# Proto_ARM.net
KiCad netlist of a schematic drawn in EAGLE
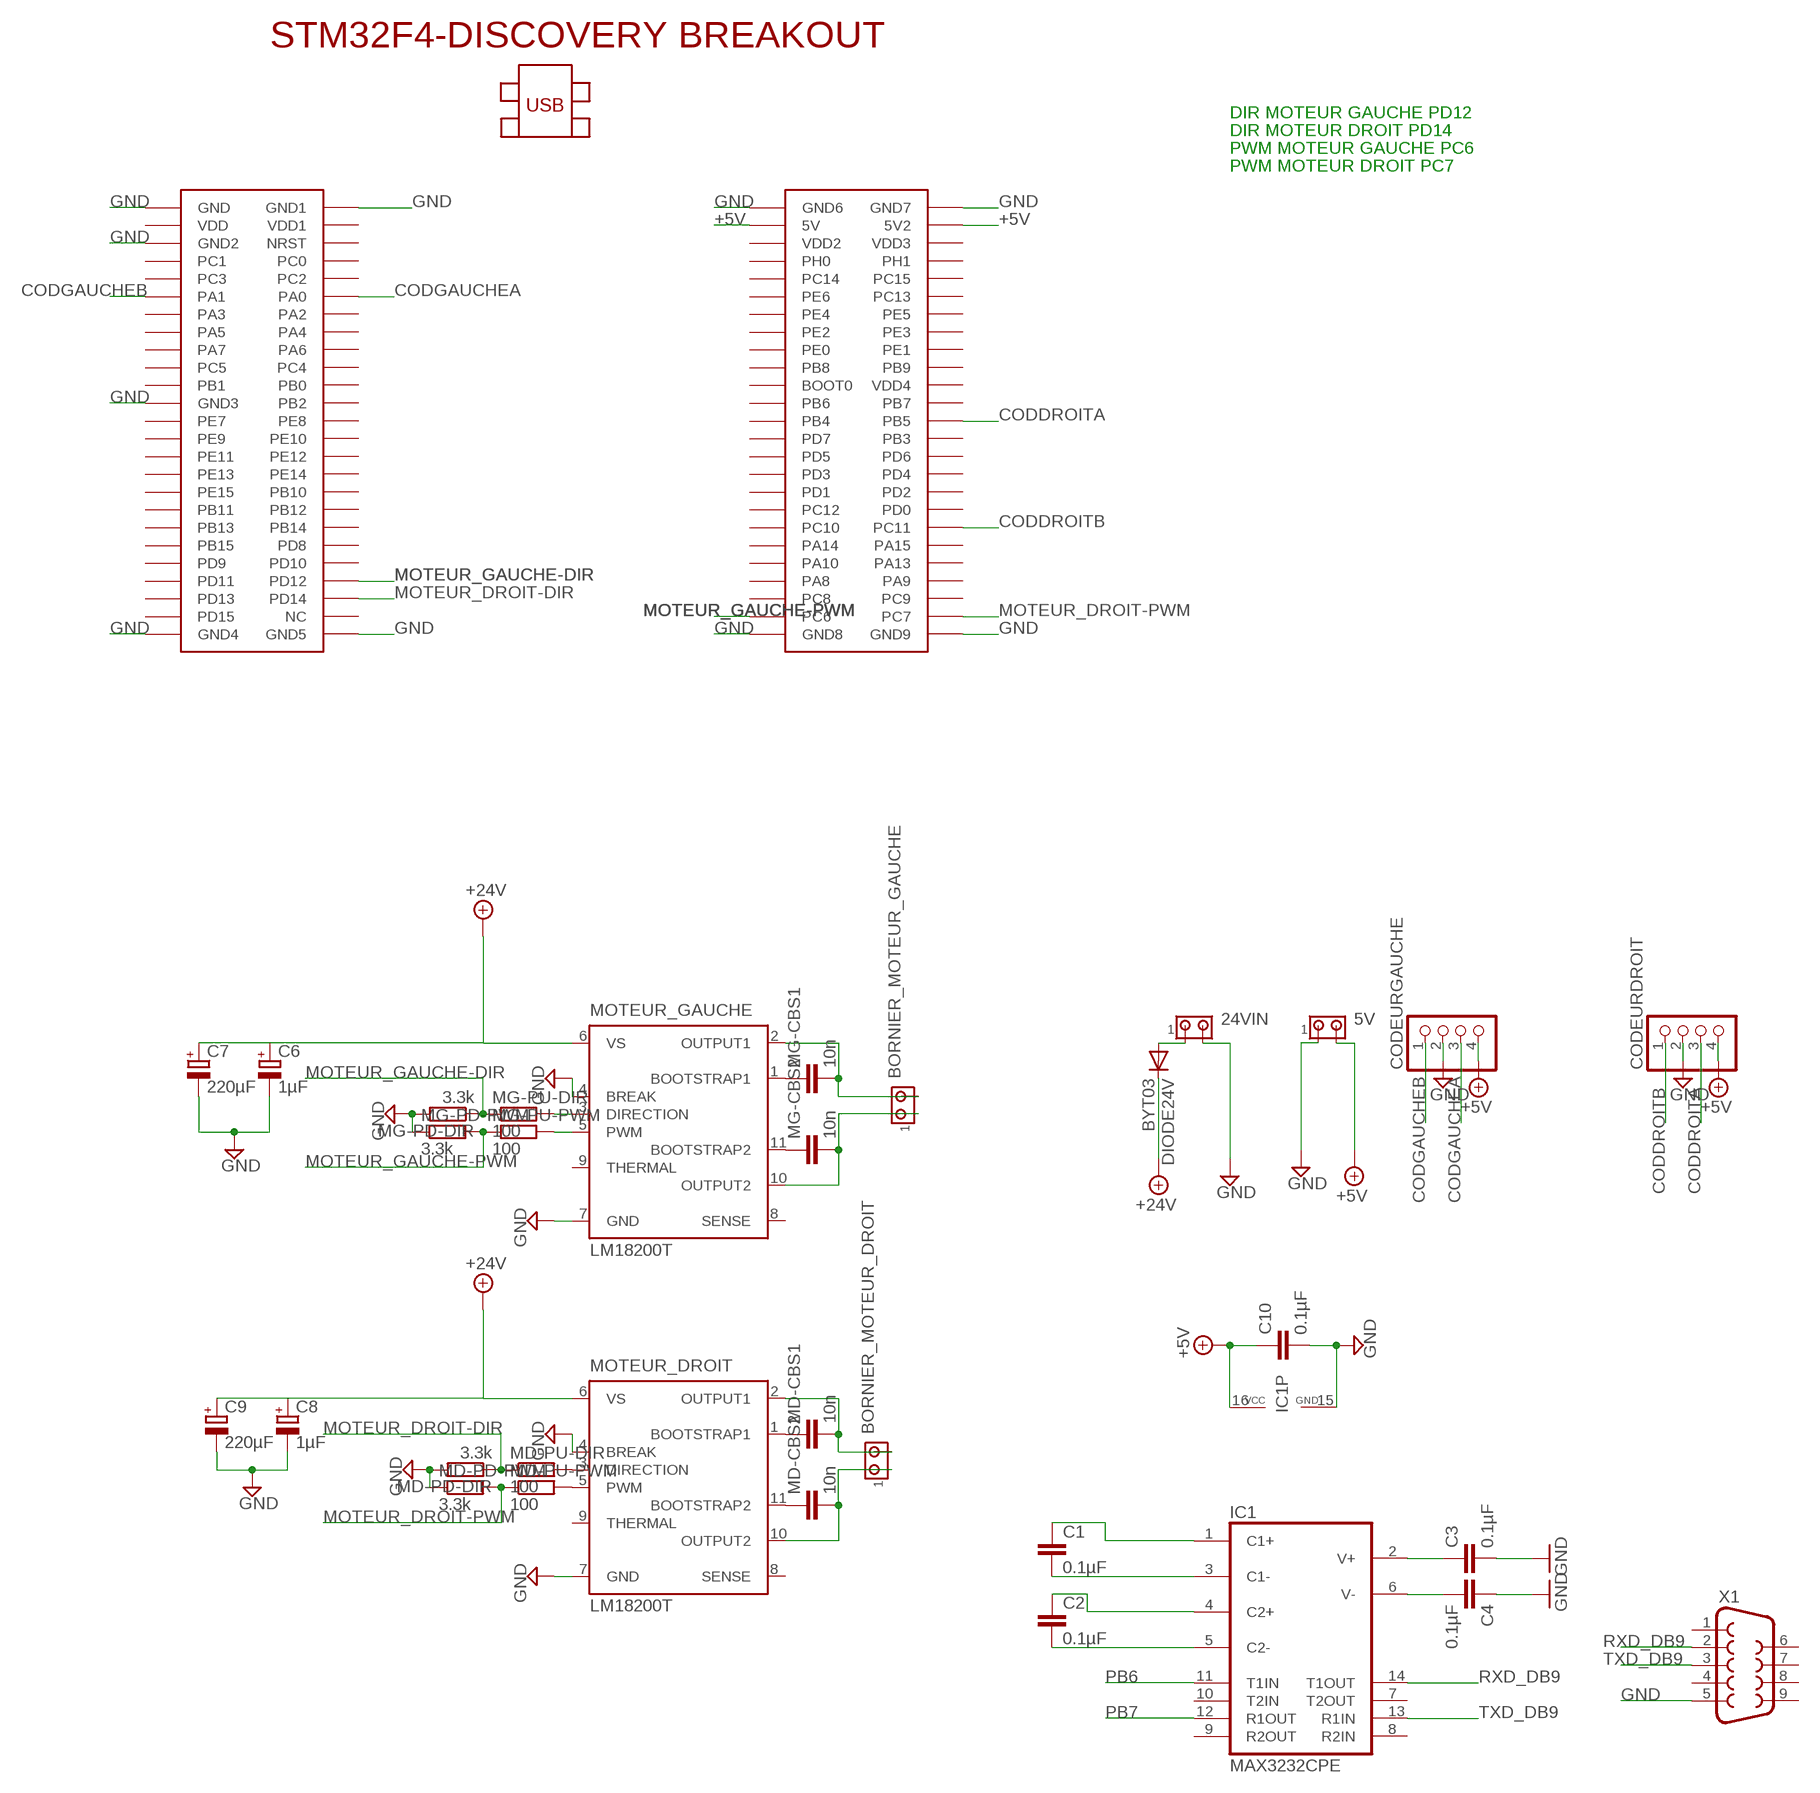
[diagram p0: schematic, sheet 1]

(export (version "E")
  (design (tool "Eeschema 10.0.6"))
  (components
    (comp (ref "5V")
      (value "MTA02-156")
      (footprint "eagle-import:1X2MTA")
      (libsource (lib "eagle-import") (part "MTA02-156"))
    )
    (comp (ref "24VIN")
      (value "MTA02-156")
      (footprint "eagle-import:1X2MTA")
      (libsource (lib "eagle-import") (part "MTA02-156"))
    )
    (comp (ref "BORNIER_MOTEUR_DROIT")
      (value "MTA02-156")
      (footprint "eagle-import:1X2MTA")
      (libsource (lib "eagle-import") (part "MTA02-156"))
    )
    (comp (ref "BORNIER_MOTEUR_GAUCHE")
      (value "MTA02-156")
      (footprint "eagle-import:1X2MTA")
      (libsource (lib "eagle-import") (part "MTA02-156"))
    )
    (comp (ref "C1")
      (value "0.1µF")
      (footprint "eagle-import:C050-035X075")
      (libsource (lib "eagle-import") (part "C-EU050-035X075"))
    )
    (comp (ref "C2")
      (value "0.1µF")
      (footprint "eagle-import:C050-035X075")
      (libsource (lib "eagle-import") (part "C-EU050-035X075"))
    )
    (comp (ref "C3")
      (value "0.1µF")
      (footprint "eagle-import:C050-035X075")
      (libsource (lib "eagle-import") (part "C-EU050-035X075"))
    )
    (comp (ref "C4")
      (value "0.1µF")
      (footprint "eagle-import:C050-035X075")
      (libsource (lib "eagle-import") (part "C-EU050-035X075"))
    )
    (comp (ref "C6")
      (value "1µF")
      (footprint "eagle-import:E3,5-8")
      (libsource (lib "eagle-import") (part "CPOL-EUE3.5-8"))
    )
    (comp (ref "C7")
      (value "220µF")
      (footprint "eagle-import:E3,5-8")
      (libsource (lib "eagle-import") (part "CPOL-EUE3.5-8"))
    )
    (comp (ref "C8")
      (value "1µF")
      (footprint "eagle-import:E3,5-8")
      (libsource (lib "eagle-import") (part "CPOL-EUE3.5-8"))
    )
    (comp (ref "C9")
      (value "220µF")
      (footprint "eagle-import:E3,5-8")
      (libsource (lib "eagle-import") (part "CPOL-EUE3.5-8"))
    )
    (comp (ref "C10")
      (value "0.1µF")
      (footprint "eagle-import:C050-035X075")
      (libsource (lib "eagle-import") (part "C-EU050-035X075"))
    )
    (comp (ref "CODEURDROIT")
      (value "PINHD-1X4")
      (footprint "eagle-import:1X04")
      (libsource (lib "eagle-import") (part "PINHD-1X4"))
    )
    (comp (ref "CODEURGAUCHE")
      (value "PINHD-1X4")
      (footprint "eagle-import:1X04")
      (libsource (lib "eagle-import") (part "PINHD-1X4"))
    )
    (comp (ref "DIODE24V")
      (value "BYT03")
      (footprint "eagle-import:DO27-15")
      (libsource (lib "eagle-import") (part "BYT03"))
    )
    (comp (ref "IC1")
      (value "MAX3232CPE")
      (footprint "eagle-import:DIL16")
      (fields
        (field (name "MF") "MAXIM")
        (field (name "MPN") "MAX3232CPE+")
        (field (name "MF_1") "MAXIM")
        (field (name "MPN_1") "MAX3232CPE+")
        (field (name "OC_FARNELL") "9724494")
        (field (name "OC_NEWARK") "68K4626")
      )
      (libsource (lib "eagle-import") (part "MAX3232PEC"))
    )
    (comp (ref "MD-CBS1")
      (value "10n")
      (footprint "eagle-import:C050-025X075")
      (libsource (lib "eagle-import") (part "C-EU050-025X075"))
    )
    (comp (ref "MD-CBS2")
      (value "10n")
      (footprint "eagle-import:C050-025X075")
      (libsource (lib "eagle-import") (part "C-EU050-025X075"))
    )
    (comp (ref "MD-PD-DIR")
      (value "3.3k")
      (footprint "eagle-import:0207_7")
      (libsource (lib "eagle-import") (part "R-EU_0207/7"))
    )
    (comp (ref "MD-PD-PWM")
      (value "3.3k")
      (footprint "eagle-import:0207_7")
      (libsource (lib "eagle-import") (part "R-EU_0207/7"))
    )
    (comp (ref "MD-PU-DIR")
      (value "100")
      (footprint "eagle-import:0207_7")
      (libsource (lib "eagle-import") (part "R-EU_0207/7"))
    )
    (comp (ref "MD-PU-PWM")
      (value "100")
      (footprint "eagle-import:0207_7")
      (libsource (lib "eagle-import") (part "R-EU_0207/7"))
    )
    (comp (ref "MG-CBS1")
      (value "10n")
      (footprint "eagle-import:C050-025X075")
      (libsource (lib "eagle-import") (part "C-EU050-025X075"))
    )
    (comp (ref "MG-CBS2")
      (value "10n")
      (footprint "eagle-import:C050-025X075")
      (libsource (lib "eagle-import") (part "C-EU050-025X075"))
    )
    (comp (ref "MG-PD-DIR")
      (value "3.3k")
      (footprint "eagle-import:0207_7")
      (libsource (lib "eagle-import") (part "R-EU_0207/7"))
    )
    (comp (ref "MG-PD-PWM")
      (value "3.3k")
      (footprint "eagle-import:0207_7")
      (libsource (lib "eagle-import") (part "R-EU_0207/7"))
    )
    (comp (ref "MG-PU-DIR")
      (value "100")
      (footprint "eagle-import:0207_7")
      (libsource (lib "eagle-import") (part "R-EU_0207/7"))
    )
    (comp (ref "MG-PU-PWM")
      (value "100")
      (footprint "eagle-import:0207_7")
      (libsource (lib "eagle-import") (part "R-EU_0207/7"))
    )
    (comp (ref "MOTEUR_DROIT")
      (value "LM18200T")
      (footprint "eagle-import:TO-220-11")
      (libsource (lib "eagle-import") (part "LM18200T"))
    )
    (comp (ref "MOTEUR_GAUCHE")
      (value "LM18200T")
      (footprint "eagle-import:TO-220-11")
      (libsource (lib "eagle-import") (part "LM18200T"))
    )
    (comp (ref "U$1")
      (value "STM32F4-DISCOVERY")
      (footprint "eagle-import:STM32F4-DISCOVERY")
      (libsource (lib "eagle-import") (part "STM32F4-DISCOVERY"))
    )
    (comp (ref "X1")
      (value "F09HP")
      (footprint "eagle-import:F09HP")
      (libsource (lib "eagle-import") (part "F09HP"))
    )
  )
  (nets
    (net (code "1") (name "+5V") (class "Default")
      (node (ref "5V") (pin "2") (pinfunction "2_2") (pintype "passive"))
      (node (ref "C10") (pin "1") (pinfunction "1_1") (pintype "passive"))
      (node (ref "CODEURDROIT") (pin "4") (pinfunction "4_4") (pintype "passive"))
      (node (ref "CODEURGAUCHE") (pin "4") (pinfunction "4_4") (pintype "passive"))
      (node (ref "IC1") (pin "16") (pinfunction "VCC_16") (pintype "power_in"))
      (node (ref "U$1") (pin "P$53") (pinfunction "5V_P$53") (pintype "bidirectional"))
      (node (ref "U$1") (pin "P$54") (pinfunction "5V2_P$54") (pintype "bidirectional"))
    )
    (net (code "2") (name "+24V") (class "Default")
      (node (ref "C6") (pin "+") (pinfunction "+_+") (pintype "passive"))
      (node (ref "C7") (pin "+") (pinfunction "+_+") (pintype "passive"))
      (node (ref "C8") (pin "+") (pinfunction "+_+") (pintype "passive"))
      (node (ref "C9") (pin "+") (pinfunction "+_+") (pintype "passive"))
      (node (ref "DIODE24V") (pin "C") (pinfunction "C_C") (pintype "passive"))
      (node (ref "MOTEUR_DROIT") (pin "6") (pinfunction "VS_6") (pintype "power_in"))
      (node (ref "MOTEUR_GAUCHE") (pin "6") (pinfunction "VS_6") (pintype "power_in"))
    )
    (net (code "3") (name "/CODDROITA") (class "Default")
      (node (ref "CODEURDROIT") (pin "3") (pinfunction "3_3") (pintype "passive"))
      (node (ref "U$1") (pin "P$76") (pinfunction "PB5_P$76") (pintype "bidirectional"))
    )
    (net (code "4") (name "/CODDROITB") (class "Default")
      (node (ref "CODEURDROIT") (pin "1") (pinfunction "1_1") (pintype "passive"))
      (node (ref "U$1") (pin "P$88") (pinfunction "PC11_P$88") (pintype "bidirectional"))
    )
    (net (code "5") (name "/CODGAUCHEA") (class "Default")
      (node (ref "CODEURGAUCHE") (pin "3") (pinfunction "3_3") (pintype "passive"))
      (node (ref "U$1") (pin "P$12") (pinfunction "PA0_P$12") (pintype "bidirectional"))
    )
    (net (code "6") (name "/CODGAUCHEB") (class "Default")
      (node (ref "CODEURGAUCHE") (pin "1") (pinfunction "1_1") (pintype "passive"))
      (node (ref "U$1") (pin "P$11") (pinfunction "PA1_P$11") (pintype "bidirectional"))
    )
    (net (code "7") (name "/MOTEUR_DROIT-DIR") (class "Default")
      (node (ref "MD-PD-DIR") (pin "1") (pinfunction "1_1") (pintype "passive"))
      (node (ref "MD-PU-DIR") (pin "1") (pinfunction "1_1") (pintype "passive"))
      (node (ref "U$1") (pin "P$46") (pinfunction "PD14_P$46") (pintype "bidirectional"))
    )
    (net (code "8") (name "/MOTEUR_DROIT-PWM") (class "Default")
      (node (ref "MD-PD-PWM") (pin "2") (pinfunction "2_2") (pintype "passive"))
      (node (ref "MD-PU-PWM") (pin "1") (pinfunction "1_1") (pintype "passive"))
      (node (ref "U$1") (pin "P$98") (pinfunction "PC7_P$98") (pintype "bidirectional"))
    )
    (net (code "9") (name "/MOTEUR_GAUCHE-DIR") (class "Default")
      (node (ref "MG-PD-DIR") (pin "1") (pinfunction "1_1") (pintype "passive"))
      (node (ref "MG-PU-DIR") (pin "1") (pinfunction "1_1") (pintype "passive"))
      (node (ref "U$1") (pin "P$44") (pinfunction "PD12_P$44") (pintype "bidirectional"))
    )
    (net (code "10") (name "/MOTEUR_GAUCHE-PWM") (class "Default")
      (node (ref "MG-PD-PWM") (pin "2") (pinfunction "2_2") (pintype "passive"))
      (node (ref "MG-PU-PWM") (pin "1") (pinfunction "1_1") (pintype "passive"))
      (node (ref "U$1") (pin "P$97") (pinfunction "PC6_P$97") (pintype "bidirectional"))
    )
    (net (code "11") (name "/PB6") (class "Default")
      (node (ref "IC1") (pin "11") (pinfunction "T1IN_11") (pintype "input"))
    )
    (net (code "12") (name "/PB7") (class "Default")
      (node (ref "IC1") (pin "12") (pinfunction "R1OUT_12") (pintype "output"))
    )
    (net (code "13") (name "/RXD_DB9") (class "Default")
      (node (ref "IC1") (pin "14") (pinfunction "T1OUT_14") (pintype "output"))
      (node (ref "X1") (pin "2") (pinfunction "2_2") (pintype "passive"))
    )
    (net (code "14") (name "/TXD_DB9") (class "Default")
      (node (ref "IC1") (pin "13") (pinfunction "R1IN_13") (pintype "input"))
      (node (ref "X1") (pin "3") (pinfunction "3_3") (pintype "passive"))
    )
    (net (code "15") (name "GND") (class "Default")
      (node (ref "24VIN") (pin "2") (pinfunction "2_2") (pintype "passive"))
      (node (ref "5V") (pin "1") (pinfunction "1_1") (pintype "passive"))
      (node (ref "C10") (pin "2") (pinfunction "2_2") (pintype "passive"))
      (node (ref "C3") (pin "2") (pinfunction "2_2") (pintype "passive"))
      (node (ref "C4") (pin "1") (pinfunction "1_1") (pintype "passive"))
      (node (ref "C6") (pin "-") (pinfunction "-_-") (pintype "passive"))
      (node (ref "C7") (pin "-") (pinfunction "-_-") (pintype "passive"))
      (node (ref "C8") (pin "-") (pinfunction "-_-") (pintype "passive"))
      (node (ref "C9") (pin "-") (pinfunction "-_-") (pintype "passive"))
      (node (ref "CODEURDROIT") (pin "2") (pinfunction "2_2") (pintype "passive"))
      (node (ref "CODEURGAUCHE") (pin "2") (pinfunction "2_2") (pintype "passive"))
      (node (ref "IC1") (pin "15") (pinfunction "GND_15") (pintype "power_in"))
      (node (ref "MD-PD-DIR") (pin "2") (pinfunction "2_2") (pintype "passive"))
      (node (ref "MD-PD-PWM") (pin "1") (pinfunction "1_1") (pintype "passive"))
      (node (ref "MG-PD-DIR") (pin "2") (pinfunction "2_2") (pintype "passive"))
      (node (ref "MG-PD-PWM") (pin "1") (pinfunction "1_1") (pintype "passive"))
      (node (ref "MOTEUR_DROIT") (pin "4") (pinfunction "BREAK_4") (pintype "input"))
      (node (ref "MOTEUR_DROIT") (pin "7") (pinfunction "GND_7") (pintype "power_in"))
      (node (ref "MOTEUR_GAUCHE") (pin "4") (pinfunction "BREAK_4") (pintype "input"))
      (node (ref "MOTEUR_GAUCHE") (pin "7") (pinfunction "GND_7") (pintype "power_in"))
      (node (ref "U$1") (pin "P$1") (pinfunction "GND_P$1") (pintype "bidirectional"))
      (node (ref "U$1") (pin "P$100") (pinfunction "GND9_P$100") (pintype "bidirectional"))
      (node (ref "U$1") (pin "P$2") (pinfunction "GND1_P$2") (pintype "bidirectional"))
      (node (ref "U$1") (pin "P$23") (pinfunction "GND3_P$23") (pintype "bidirectional"))
      (node (ref "U$1") (pin "P$49") (pinfunction "GND4_P$49") (pintype "bidirectional"))
      (node (ref "U$1") (pin "P$5") (pinfunction "GND2_P$5") (pintype "bidirectional"))
      (node (ref "U$1") (pin "P$50") (pinfunction "GND5_P$50") (pintype "bidirectional"))
      (node (ref "U$1") (pin "P$51") (pinfunction "GND6_P$51") (pintype "bidirectional"))
      (node (ref "U$1") (pin "P$52") (pinfunction "GND7_P$52") (pintype "bidirectional"))
      (node (ref "U$1") (pin "P$99") (pinfunction "GND8_P$99") (pintype "bidirectional"))
      (node (ref "X1") (pin "5") (pinfunction "5_5") (pintype "passive"))
    )
    (net (code "16") (name "Net-(24VIN-Pad1)") (class "Default")
      (node (ref "24VIN") (pin "1") (pinfunction "1_1") (pintype "passive"))
      (node (ref "DIODE24V") (pin "A") (pinfunction "A_A") (pintype "passive"))
    )
    (net (code "17") (name "Net-(IC1A-C1+)") (class "Default")
      (node (ref "C1") (pin "1") (pinfunction "1_1") (pintype "passive"))
      (node (ref "IC1") (pin "1") (pinfunction "C1+_1") (pintype "bidirectional"))
    )
    (net (code "18") (name "Net-(IC1A-C1-)") (class "Default")
      (node (ref "C1") (pin "2") (pinfunction "2_2") (pintype "passive"))
      (node (ref "IC1") (pin "3") (pinfunction "C1-_3") (pintype "bidirectional"))
    )
    (net (code "19") (name "Net-(IC1A-C2+)") (class "Default")
      (node (ref "C2") (pin "1") (pinfunction "1_1") (pintype "passive"))
      (node (ref "IC1") (pin "4") (pinfunction "C2+_4") (pintype "bidirectional"))
    )
    (net (code "20") (name "Net-(IC1A-C2-)") (class "Default")
      (node (ref "C2") (pin "2") (pinfunction "2_2") (pintype "passive"))
      (node (ref "IC1") (pin "5") (pinfunction "C2-_5") (pintype "bidirectional"))
    )
    (net (code "21") (name "Net-(IC1A-V+)") (class "Default")
      (node (ref "C3") (pin "1") (pinfunction "1_1") (pintype "passive"))
      (node (ref "IC1") (pin "2") (pinfunction "V+_2") (pintype "bidirectional"))
    )
    (net (code "22") (name "Net-(IC1A-V-)") (class "Default")
      (node (ref "C4") (pin "2") (pinfunction "2_2") (pintype "passive"))
      (node (ref "IC1") (pin "6") (pinfunction "V-_6") (pintype "bidirectional"))
    )
    (net (code "23") (name "Net-(MOTEUR_DROIT-BOOTSTRAP1)") (class "Default")
      (node (ref "MD-CBS1") (pin "1") (pinfunction "1_1") (pintype "passive"))
      (node (ref "MOTEUR_DROIT") (pin "1") (pinfunction "BOOTSTRAP1_1") (pintype "input"))
    )
    (net (code "24") (name "Net-(MOTEUR_DROIT-BOOTSTRAP2)") (class "Default")
      (node (ref "MD-CBS2") (pin "1") (pinfunction "1_1") (pintype "passive"))
      (node (ref "MOTEUR_DROIT") (pin "11") (pinfunction "BOOTSTRAP2_11") (pintype "input"))
    )
    (net (code "25") (name "Net-(MOTEUR_DROIT-DIRECTION)") (class "Default")
      (node (ref "MD-PU-DIR") (pin "2") (pinfunction "2_2") (pintype "passive"))
      (node (ref "MOTEUR_DROIT") (pin "3") (pinfunction "DIRECTION_3") (pintype "input"))
    )
    (net (code "26") (name "Net-(MOTEUR_DROIT-OUTPUT1)") (class "Default")
      (node (ref "BORNIER_MOTEUR_DROIT") (pin "2") (pinfunction "2_2") (pintype "passive"))
      (node (ref "MD-CBS1") (pin "2") (pinfunction "2_2") (pintype "passive"))
      (node (ref "MOTEUR_DROIT") (pin "2") (pinfunction "OUTPUT1_2") (pintype "output"))
    )
    (net (code "27") (name "Net-(MOTEUR_DROIT-OUTPUT2)") (class "Default")
      (node (ref "BORNIER_MOTEUR_DROIT") (pin "1") (pinfunction "1_1") (pintype "passive"))
      (node (ref "MD-CBS2") (pin "2") (pinfunction "2_2") (pintype "passive"))
      (node (ref "MOTEUR_DROIT") (pin "10") (pinfunction "OUTPUT2_10") (pintype "output"))
    )
    (net (code "28") (name "Net-(MOTEUR_DROIT-PWM)") (class "Default")
      (node (ref "MD-PU-PWM") (pin "2") (pinfunction "2_2") (pintype "passive"))
      (node (ref "MOTEUR_DROIT") (pin "5") (pinfunction "PWM_5") (pintype "input"))
    )
    (net (code "29") (name "Net-(MOTEUR_GAUCHE-BOOTSTRAP1)") (class "Default")
      (node (ref "MG-CBS1") (pin "1") (pinfunction "1_1") (pintype "passive"))
      (node (ref "MOTEUR_GAUCHE") (pin "1") (pinfunction "BOOTSTRAP1_1") (pintype "input"))
    )
    (net (code "30") (name "Net-(MOTEUR_GAUCHE-BOOTSTRAP2)") (class "Default")
      (node (ref "MG-CBS2") (pin "1") (pinfunction "1_1") (pintype "passive"))
      (node (ref "MOTEUR_GAUCHE") (pin "11") (pinfunction "BOOTSTRAP2_11") (pintype "input"))
    )
    (net (code "31") (name "Net-(MOTEUR_GAUCHE-DIRECTION)") (class "Default")
      (node (ref "MG-PU-DIR") (pin "2") (pinfunction "2_2") (pintype "passive"))
      (node (ref "MOTEUR_GAUCHE") (pin "3") (pinfunction "DIRECTION_3") (pintype "input"))
    )
    (net (code "32") (name "Net-(MOTEUR_GAUCHE-OUTPUT1)") (class "Default")
      (node (ref "BORNIER_MOTEUR_GAUCHE") (pin "2") (pinfunction "2_2") (pintype "passive"))
      (node (ref "MG-CBS1") (pin "2") (pinfunction "2_2") (pintype "passive"))
      (node (ref "MOTEUR_GAUCHE") (pin "2") (pinfunction "OUTPUT1_2") (pintype "output"))
    )
    (net (code "33") (name "Net-(MOTEUR_GAUCHE-OUTPUT2)") (class "Default")
      (node (ref "BORNIER_MOTEUR_GAUCHE") (pin "1") (pinfunction "1_1") (pintype "passive"))
      (node (ref "MG-CBS2") (pin "2") (pinfunction "2_2") (pintype "passive"))
      (node (ref "MOTEUR_GAUCHE") (pin "10") (pinfunction "OUTPUT2_10") (pintype "output"))
    )
    (net (code "34") (name "Net-(MOTEUR_GAUCHE-PWM)") (class "Default")
      (node (ref "MG-PU-PWM") (pin "2") (pinfunction "2_2") (pintype "passive"))
      (node (ref "MOTEUR_GAUCHE") (pin "5") (pinfunction "PWM_5") (pintype "input"))
    )
    (net (code "35") (name "unconnected-(IC1A-R2IN-Pad8)") (class "Default")
      (node (ref "IC1") (pin "8") (pinfunction "R2IN_8") (pintype "input"))
    )
    (net (code "36") (name "unconnected-(IC1A-R2OUT-Pad9)") (class "Default")
      (node (ref "IC1") (pin "9") (pinfunction "R2OUT_9") (pintype "output"))
    )
    (net (code "37") (name "unconnected-(IC1A-T2IN-Pad10)") (class "Default")
      (node (ref "IC1") (pin "10") (pinfunction "T2IN_10") (pintype "input"))
    )
    (net (code "38") (name "unconnected-(IC1A-T2OUT-Pad7)") (class "Default")
      (node (ref "IC1") (pin "7") (pinfunction "T2OUT_7") (pintype "output"))
    )
    (net (code "39") (name "unconnected-(MOTEUR_DROIT-SENSE-Pad8)") (class "Default")
      (node (ref "MOTEUR_DROIT") (pin "8") (pinfunction "SENSE_8") (pintype "output"))
    )
    (net (code "40") (name "unconnected-(MOTEUR_DROIT-THERMAL-Pad9)") (class "Default")
      (node (ref "MOTEUR_DROIT") (pin "9") (pinfunction "THERMAL_9") (pintype "output"))
    )
    (net (code "41") (name "unconnected-(MOTEUR_GAUCHE-SENSE-Pad8)") (class "Default")
      (node (ref "MOTEUR_GAUCHE") (pin "8") (pinfunction "SENSE_8") (pintype "output"))
    )
    (net (code "42") (name "unconnected-(MOTEUR_GAUCHE-THERMAL-Pad9)") (class "Default")
      (node (ref "MOTEUR_GAUCHE") (pin "9") (pinfunction "THERMAL_9") (pintype "output"))
    )
    (net (code "43") (name "unconnected-(U$1-BOOT0-PadP$71)") (class "Default")
      (node (ref "U$1") (pin "P$71") (pinfunction "BOOT0_P$71") (pintype "bidirectional"))
    )
    (net (code "44") (name "unconnected-(U$1-NC-PadP$48)") (class "Default")
      (node (ref "U$1") (pin "P$48") (pinfunction "NC_P$48") (pintype "bidirectional"))
    )
    (net (code "45") (name "unconnected-(U$1-NRST-PadP$6)") (class "Default")
      (node (ref "U$1") (pin "P$6") (pinfunction "NRST_P$6") (pintype "bidirectional"))
    )
    (net (code "46") (name "unconnected-(U$1-PA2-PadP$14)") (class "Default")
      (node (ref "U$1") (pin "P$14") (pinfunction "PA2_P$14") (pintype "bidirectional"))
    )
    (net (code "47") (name "unconnected-(U$1-PA3-PadP$13)") (class "Default")
      (node (ref "U$1") (pin "P$13") (pinfunction "PA3_P$13") (pintype "bidirectional"))
    )
    (net (code "48") (name "unconnected-(U$1-PA4-PadP$16)") (class "Default")
      (node (ref "U$1") (pin "P$16") (pinfunction "PA4_P$16") (pintype "bidirectional"))
    )
    (net (code "49") (name "unconnected-(U$1-PA5-PadP$15)") (class "Default")
      (node (ref "U$1") (pin "P$15") (pinfunction "PA5_P$15") (pintype "bidirectional"))
    )
    (net (code "50") (name "unconnected-(U$1-PA6-PadP$18)") (class "Default")
      (node (ref "U$1") (pin "P$18") (pinfunction "PA6_P$18") (pintype "bidirectional"))
    )
    (net (code "51") (name "unconnected-(U$1-PA7-PadP$17)") (class "Default")
      (node (ref "U$1") (pin "P$17") (pinfunction "PA7_P$17") (pintype "bidirectional"))
    )
    (net (code "52") (name "unconnected-(U$1-PA8-PadP$93)") (class "Default")
      (node (ref "U$1") (pin "P$93") (pinfunction "PA8_P$93") (pintype "bidirectional"))
    )
    (net (code "53") (name "unconnected-(U$1-PA9-PadP$94)") (class "Default")
      (node (ref "U$1") (pin "P$94") (pinfunction "PA9_P$94") (pintype "bidirectional"))
    )
    (net (code "54") (name "unconnected-(U$1-PA10-PadP$91)") (class "Default")
      (node (ref "U$1") (pin "P$91") (pinfunction "PA10_P$91") (pintype "bidirectional"))
    )
    (net (code "55") (name "unconnected-(U$1-PA13-PadP$92)") (class "Default")
      (node (ref "U$1") (pin "P$92") (pinfunction "PA13_P$92") (pintype "bidirectional"))
    )
    (net (code "56") (name "unconnected-(U$1-PA14-PadP$89)") (class "Default")
      (node (ref "U$1") (pin "P$89") (pinfunction "PA14_P$89") (pintype "bidirectional"))
    )
    (net (code "57") (name "unconnected-(U$1-PA15-PadP$90)") (class "Default")
      (node (ref "U$1") (pin "P$90") (pinfunction "PA15_P$90") (pintype "bidirectional"))
    )
    (net (code "58") (name "unconnected-(U$1-PB0-PadP$22)") (class "Default")
      (node (ref "U$1") (pin "P$22") (pinfunction "PB0_P$22") (pintype "bidirectional"))
    )
    (net (code "59") (name "unconnected-(U$1-PB1-PadP$21)") (class "Default")
      (node (ref "U$1") (pin "P$21") (pinfunction "PB1_P$21") (pintype "bidirectional"))
    )
    (net (code "60") (name "unconnected-(U$1-PB2-PadP$24)") (class "Default")
      (node (ref "U$1") (pin "P$24") (pinfunction "PB2_P$24") (pintype "bidirectional"))
    )
    (net (code "61") (name "unconnected-(U$1-PB3-PadP$78)") (class "Default")
      (node (ref "U$1") (pin "P$78") (pinfunction "PB3_P$78") (pintype "bidirectional"))
    )
    (net (code "62") (name "unconnected-(U$1-PB4-PadP$75)") (class "Default")
      (node (ref "U$1") (pin "P$75") (pinfunction "PB4_P$75") (pintype "bidirectional"))
    )
    (net (code "63") (name "unconnected-(U$1-PB6-PadP$73)") (class "Default")
      (node (ref "U$1") (pin "P$73") (pinfunction "PB6_P$73") (pintype "bidirectional"))
    )
    (net (code "64") (name "unconnected-(U$1-PB7-PadP$74)") (class "Default")
      (node (ref "U$1") (pin "P$74") (pinfunction "PB7_P$74") (pintype "bidirectional"))
    )
    (net (code "65") (name "unconnected-(U$1-PB8-PadP$69)") (class "Default")
      (node (ref "U$1") (pin "P$69") (pinfunction "PB8_P$69") (pintype "bidirectional"))
    )
    (net (code "66") (name "unconnected-(U$1-PB9-PadP$70)") (class "Default")
      (node (ref "U$1") (pin "P$70") (pinfunction "PB9_P$70") (pintype "bidirectional"))
    )
    (net (code "67") (name "unconnected-(U$1-PB10-PadP$34)") (class "Default")
      (node (ref "U$1") (pin "P$34") (pinfunction "PB10_P$34") (pintype "bidirectional"))
    )
    (net (code "68") (name "unconnected-(U$1-PB11-PadP$35)") (class "Default")
      (node (ref "U$1") (pin "P$35") (pinfunction "PB11_P$35") (pintype "bidirectional"))
    )
    (net (code "69") (name "unconnected-(U$1-PB12-PadP$36)") (class "Default")
      (node (ref "U$1") (pin "P$36") (pinfunction "PB12_P$36") (pintype "bidirectional"))
    )
    (net (code "70") (name "unconnected-(U$1-PB13-PadP$37)") (class "Default")
      (node (ref "U$1") (pin "P$37") (pinfunction "PB13_P$37") (pintype "bidirectional"))
    )
    (net (code "71") (name "unconnected-(U$1-PB14-PadP$38)") (class "Default")
      (node (ref "U$1") (pin "P$38") (pinfunction "PB14_P$38") (pintype "bidirectional"))
    )
    (net (code "72") (name "unconnected-(U$1-PB15-PadP$39)") (class "Default")
      (node (ref "U$1") (pin "P$39") (pinfunction "PB15_P$39") (pintype "bidirectional"))
    )
    (net (code "73") (name "unconnected-(U$1-PC0-PadP$8)") (class "Default")
      (node (ref "U$1") (pin "P$8") (pinfunction "PC0_P$8") (pintype "bidirectional"))
    )
    (net (code "74") (name "unconnected-(U$1-PC1-PadP$7)") (class "Default")
      (node (ref "U$1") (pin "P$7") (pinfunction "PC1_P$7") (pintype "bidirectional"))
    )
    (net (code "75") (name "unconnected-(U$1-PC2-PadP$10)") (class "Default")
      (node (ref "U$1") (pin "P$10") (pinfunction "PC2_P$10") (pintype "bidirectional"))
    )
    (net (code "76") (name "unconnected-(U$1-PC3-PadP$9)") (class "Default")
      (node (ref "U$1") (pin "P$9") (pinfunction "PC3_P$9") (pintype "bidirectional"))
    )
    (net (code "77") (name "unconnected-(U$1-PC4-PadP$20)") (class "Default")
      (node (ref "U$1") (pin "P$20") (pinfunction "PC4_P$20") (pintype "bidirectional"))
    )
    (net (code "78") (name "unconnected-(U$1-PC5-PadP$19)") (class "Default")
      (node (ref "U$1") (pin "P$19") (pinfunction "PC5_P$19") (pintype "bidirectional"))
    )
    (net (code "79") (name "unconnected-(U$1-PC8-PadP$95)") (class "Default")
      (node (ref "U$1") (pin "P$95") (pinfunction "PC8_P$95") (pintype "bidirectional"))
    )
    (net (code "80") (name "unconnected-(U$1-PC9-PadP$96)") (class "Default")
      (node (ref "U$1") (pin "P$96") (pinfunction "PC9_P$96") (pintype "bidirectional"))
    )
    (net (code "81") (name "unconnected-(U$1-PC10-PadP$87)") (class "Default")
      (node (ref "U$1") (pin "P$87") (pinfunction "PC10_P$87") (pintype "bidirectional"))
    )
    (net (code "82") (name "unconnected-(U$1-PC12-PadP$85)") (class "Default")
      (node (ref "U$1") (pin "P$85") (pinfunction "PC12_P$85") (pintype "bidirectional"))
    )
    (net (code "83") (name "unconnected-(U$1-PC13-PadP$62)") (class "Default")
      (node (ref "U$1") (pin "P$62") (pinfunction "PC13_P$62") (pintype "bidirectional"))
    )
    (net (code "84") (name "unconnected-(U$1-PC14-PadP$59)") (class "Default")
      (node (ref "U$1") (pin "P$59") (pinfunction "PC14_P$59") (pintype "bidirectional"))
    )
    (net (code "85") (name "unconnected-(U$1-PC15-PadP$60)") (class "Default")
      (node (ref "U$1") (pin "P$60") (pinfunction "PC15_P$60") (pintype "bidirectional"))
    )
    (net (code "86") (name "unconnected-(U$1-PD0-PadP$86)") (class "Default")
      (node (ref "U$1") (pin "P$86") (pinfunction "PD0_P$86") (pintype "bidirectional"))
    )
    (net (code "87") (name "unconnected-(U$1-PD1-PadP$83)") (class "Default")
      (node (ref "U$1") (pin "P$83") (pinfunction "PD1_P$83") (pintype "bidirectional"))
    )
    (net (code "88") (name "unconnected-(U$1-PD2-PadP$84)") (class "Default")
      (node (ref "U$1") (pin "P$84") (pinfunction "PD2_P$84") (pintype "bidirectional"))
    )
    (net (code "89") (name "unconnected-(U$1-PD3-PadP$81)") (class "Default")
      (node (ref "U$1") (pin "P$81") (pinfunction "PD3_P$81") (pintype "bidirectional"))
    )
    (net (code "90") (name "unconnected-(U$1-PD4-PadP$82)") (class "Default")
      (node (ref "U$1") (pin "P$82") (pinfunction "PD4_P$82") (pintype "bidirectional"))
    )
    (net (code "91") (name "unconnected-(U$1-PD5-PadP$79)") (class "Default")
      (node (ref "U$1") (pin "P$79") (pinfunction "PD5_P$79") (pintype "bidirectional"))
    )
    (net (code "92") (name "unconnected-(U$1-PD6-PadP$80)") (class "Default")
      (node (ref "U$1") (pin "P$80") (pinfunction "PD6_P$80") (pintype "bidirectional"))
    )
    (net (code "93") (name "unconnected-(U$1-PD7-PadP$77)") (class "Default")
      (node (ref "U$1") (pin "P$77") (pinfunction "PD7_P$77") (pintype "bidirectional"))
    )
    (net (code "94") (name "unconnected-(U$1-PD8-PadP$40)") (class "Default")
      (node (ref "U$1") (pin "P$40") (pinfunction "PD8_P$40") (pintype "bidirectional"))
    )
    (net (code "95") (name "unconnected-(U$1-PD9-PadP$41)") (class "Default")
      (node (ref "U$1") (pin "P$41") (pinfunction "PD9_P$41") (pintype "bidirectional"))
    )
    (net (code "96") (name "unconnected-(U$1-PD10-PadP$42)") (class "Default")
      (node (ref "U$1") (pin "P$42") (pinfunction "PD10_P$42") (pintype "bidirectional"))
    )
    (net (code "97") (name "unconnected-(U$1-PD11-PadP$43)") (class "Default")
      (node (ref "U$1") (pin "P$43") (pinfunction "PD11_P$43") (pintype "bidirectional"))
    )
    (net (code "98") (name "unconnected-(U$1-PD13-PadP$45)") (class "Default")
      (node (ref "U$1") (pin "P$45") (pinfunction "PD13_P$45") (pintype "bidirectional"))
    )
    (net (code "99") (name "unconnected-(U$1-PD15-PadP$47)") (class "Default")
      (node (ref "U$1") (pin "P$47") (pinfunction "PD15_P$47") (pintype "bidirectional"))
    )
    (net (code "100") (name "unconnected-(U$1-PE0-PadP$67)") (class "Default")
      (node (ref "U$1") (pin "P$67") (pinfunction "PE0_P$67") (pintype "bidirectional"))
    )
    (net (code "101") (name "unconnected-(U$1-PE1-PadP$68)") (class "Default")
      (node (ref "U$1") (pin "P$68") (pinfunction "PE1_P$68") (pintype "bidirectional"))
    )
    (net (code "102") (name "unconnected-(U$1-PE2-PadP$65)") (class "Default")
      (node (ref "U$1") (pin "P$65") (pinfunction "PE2_P$65") (pintype "bidirectional"))
    )
    (net (code "103") (name "unconnected-(U$1-PE3-PadP$66)") (class "Default")
      (node (ref "U$1") (pin "P$66") (pinfunction "PE3_P$66") (pintype "bidirectional"))
    )
    (net (code "104") (name "unconnected-(U$1-PE4-PadP$63)") (class "Default")
      (node (ref "U$1") (pin "P$63") (pinfunction "PE4_P$63") (pintype "bidirectional"))
    )
    (net (code "105") (name "unconnected-(U$1-PE5-PadP$64)") (class "Default")
      (node (ref "U$1") (pin "P$64") (pinfunction "PE5_P$64") (pintype "bidirectional"))
    )
    (net (code "106") (name "unconnected-(U$1-PE6-PadP$61)") (class "Default")
      (node (ref "U$1") (pin "P$61") (pinfunction "PE6_P$61") (pintype "bidirectional"))
    )
    (net (code "107") (name "unconnected-(U$1-PE7-PadP$25)") (class "Default")
      (node (ref "U$1") (pin "P$25") (pinfunction "PE7_P$25") (pintype "bidirectional"))
    )
    (net (code "108") (name "unconnected-(U$1-PE8-PadP$26)") (class "Default")
      (node (ref "U$1") (pin "P$26") (pinfunction "PE8_P$26") (pintype "bidirectional"))
    )
    (net (code "109") (name "unconnected-(U$1-PE9-PadP$27)") (class "Default")
      (node (ref "U$1") (pin "P$27") (pinfunction "PE9_P$27") (pintype "bidirectional"))
    )
    (net (code "110") (name "unconnected-(U$1-PE10-PadP$28)") (class "Default")
      (node (ref "U$1") (pin "P$28") (pinfunction "PE10_P$28") (pintype "bidirectional"))
    )
    (net (code "111") (name "unconnected-(U$1-PE11-PadP$29)") (class "Default")
      (node (ref "U$1") (pin "P$29") (pinfunction "PE11_P$29") (pintype "bidirectional"))
    )
    (net (code "112") (name "unconnected-(U$1-PE12-PadP$30)") (class "Default")
      (node (ref "U$1") (pin "P$30") (pinfunction "PE12_P$30") (pintype "bidirectional"))
    )
    (net (code "113") (name "unconnected-(U$1-PE13-PadP$31)") (class "Default")
      (node (ref "U$1") (pin "P$31") (pinfunction "PE13_P$31") (pintype "bidirectional"))
    )
    (net (code "114") (name "unconnected-(U$1-PE14-PadP$32)") (class "Default")
      (node (ref "U$1") (pin "P$32") (pinfunction "PE14_P$32") (pintype "bidirectional"))
    )
    (net (code "115") (name "unconnected-(U$1-PE15-PadP$33)") (class "Default")
      (node (ref "U$1") (pin "P$33") (pinfunction "PE15_P$33") (pintype "bidirectional"))
    )
    (net (code "116") (name "unconnected-(U$1-PH0-PadP$57)") (class "Default")
      (node (ref "U$1") (pin "P$57") (pinfunction "PH0_P$57") (pintype "bidirectional"))
    )
    (net (code "117") (name "unconnected-(U$1-PH1-PadP$58)") (class "Default")
      (node (ref "U$1") (pin "P$58") (pinfunction "PH1_P$58") (pintype "bidirectional"))
    )
    (net (code "118") (name "unconnected-(U$1-VDD-PadP$3)") (class "Default")
      (node (ref "U$1") (pin "P$3") (pinfunction "VDD_P$3") (pintype "bidirectional"))
    )
    (net (code "119") (name "unconnected-(U$1-VDD1-PadP$4)") (class "Default")
      (node (ref "U$1") (pin "P$4") (pinfunction "VDD1_P$4") (pintype "bidirectional"))
    )
    (net (code "120") (name "unconnected-(U$1-VDD2-PadP$55)") (class "Default")
      (node (ref "U$1") (pin "P$55") (pinfunction "VDD2_P$55") (pintype "bidirectional"))
    )
    (net (code "121") (name "unconnected-(U$1-VDD3-PadP$56)") (class "Default")
      (node (ref "U$1") (pin "P$56") (pinfunction "VDD3_P$56") (pintype "bidirectional"))
    )
    (net (code "122") (name "unconnected-(U$1-VDD4-PadP$72)") (class "Default")
      (node (ref "U$1") (pin "P$72") (pinfunction "VDD4_P$72") (pintype "bidirectional"))
    )
    (net (code "123") (name "unconnected-(X1-Pad1)") (class "Default")
      (node (ref "X1") (pin "1") (pinfunction "1_1") (pintype "passive"))
    )
    (net (code "124") (name "unconnected-(X1-Pad4)") (class "Default")
      (node (ref "X1") (pin "4") (pinfunction "4_4") (pintype "passive"))
    )
    (net (code "125") (name "unconnected-(X1-Pad6)") (class "Default")
      (node (ref "X1") (pin "6") (pinfunction "6_6") (pintype "passive"))
    )
    (net (code "126") (name "unconnected-(X1-Pad7)") (class "Default")
      (node (ref "X1") (pin "7") (pinfunction "7_7") (pintype "passive"))
    )
    (net (code "127") (name "unconnected-(X1-Pad8)") (class "Default")
      (node (ref "X1") (pin "8") (pinfunction "8_8") (pintype "passive"))
    )
    (net (code "128") (name "unconnected-(X1-Pad9)") (class "Default")
      (node (ref "X1") (pin "9") (pinfunction "9_9") (pintype "passive"))
    )
  )
)
